# N-H-Bridge.net
KiCad netlist of a schematic drawn in EAGLE
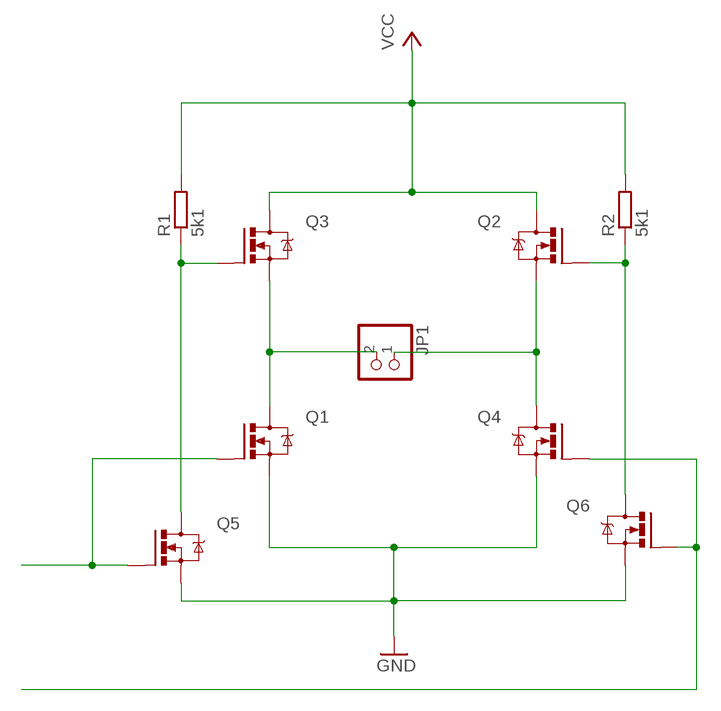
[diagram p0: schematic, sheet 1]

(export (version "E")
  (design (tool "Eeschema 10.0.6"))
  (components
    (comp (ref "JP1")
      (value "PINHD-1X2")
      (footprint "eagle-import:1X02")
      (libsource (lib "eagle-import") (part "PINHD-1X2"))
    )
    (comp (ref "Q1")
      (value "FET-NPF-2X2")
      (footprint "eagle-import:POWERFLAT-2X2")
      (libsource (lib "eagle-import") (part "FET-NPF-2X2"))
    )
    (comp (ref "Q2")
      (value "FET-NPF-2X2")
      (footprint "eagle-import:POWERFLAT-2X2")
      (libsource (lib "eagle-import") (part "FET-NPF-2X2"))
    )
    (comp (ref "Q3")
      (value "FET-NPF-2X2")
      (footprint "eagle-import:POWERFLAT-2X2")
      (libsource (lib "eagle-import") (part "FET-NPF-2X2"))
    )
    (comp (ref "Q4")
      (value "FET-NPF-2X2")
      (footprint "eagle-import:POWERFLAT-2X2")
      (libsource (lib "eagle-import") (part "FET-NPF-2X2"))
    )
    (comp (ref "Q5")
      (value "FET-NPF-2X2")
      (footprint "eagle-import:POWERFLAT-2X2")
      (libsource (lib "eagle-import") (part "FET-NPF-2X2"))
    )
    (comp (ref "Q6")
      (value "FET-NPF-2X2")
      (footprint "eagle-import:POWERFLAT-2X2")
      (libsource (lib "eagle-import") (part "FET-NPF-2X2"))
    )
    (comp (ref "R1")
      (value "5k1")
      (footprint "eagle-import:R0603")
      (libsource (lib "eagle-import") (part "R_0603"))
    )
    (comp (ref "R2")
      (value "5k1")
      (footprint "eagle-import:R0603")
      (libsource (lib "eagle-import") (part "R_0603"))
    )
  )
  (nets
    (net (code "1") (name "GND") (class "Default")
      (node (ref "Q1") (pin "S") (pinfunction "S_S") (pintype "passive"))
      (node (ref "Q1") (pin "S4") (pinfunction "S_S4") (pintype "passive"))
      (node (ref "Q4") (pin "S") (pinfunction "S_S") (pintype "passive"))
      (node (ref "Q4") (pin "S4") (pinfunction "S_S4") (pintype "passive"))
      (node (ref "Q5") (pin "S") (pinfunction "S_S") (pintype "passive"))
      (node (ref "Q5") (pin "S4") (pinfunction "S_S4") (pintype "passive"))
      (node (ref "Q6") (pin "S") (pinfunction "S_S") (pintype "passive"))
      (node (ref "Q6") (pin "S4") (pinfunction "S_S4") (pintype "passive"))
    )
    (net (code "2") (name "Net-(JP1-Pad1)") (class "Default")
      (node (ref "JP1") (pin "1") (pinfunction "1_1") (pintype "passive"))
      (node (ref "Q2") (pin "S") (pinfunction "S_S") (pintype "passive"))
      (node (ref "Q2") (pin "S4") (pinfunction "S_S4") (pintype "passive"))
      (node (ref "Q4") (pin "D") (pinfunction "D_D") (pintype "passive"))
      (node (ref "Q4") (pin "D1") (pinfunction "D_D1") (pintype "passive"))
      (node (ref "Q4") (pin "D2") (pinfunction "D_D2") (pintype "passive"))
      (node (ref "Q4") (pin "D5") (pinfunction "D_D5") (pintype "passive"))
      (node (ref "Q4") (pin "D6") (pinfunction "D_D6") (pintype "passive"))
    )
    (net (code "3") (name "Net-(JP1-Pad2)") (class "Default")
      (node (ref "JP1") (pin "2") (pinfunction "2_2") (pintype "passive"))
      (node (ref "Q1") (pin "D") (pinfunction "D_D") (pintype "passive"))
      (node (ref "Q1") (pin "D1") (pinfunction "D_D1") (pintype "passive"))
      (node (ref "Q1") (pin "D2") (pinfunction "D_D2") (pintype "passive"))
      (node (ref "Q1") (pin "D5") (pinfunction "D_D5") (pintype "passive"))
      (node (ref "Q1") (pin "D6") (pinfunction "D_D6") (pintype "passive"))
      (node (ref "Q3") (pin "S") (pinfunction "S_S") (pintype "passive"))
      (node (ref "Q3") (pin "S4") (pinfunction "S_S4") (pintype "passive"))
    )
    (net (code "4") (name "Net-(Q1-G)") (class "Default")
      (node (ref "Q1") (pin "G3") (pinfunction "G_G3") (pintype "passive"))
      (node (ref "Q5") (pin "G3") (pinfunction "G_G3") (pintype "passive"))
    )
    (net (code "5") (name "Net-(Q2-G)") (class "Default")
      (node (ref "Q2") (pin "G3") (pinfunction "G_G3") (pintype "passive"))
      (node (ref "Q6") (pin "D") (pinfunction "D_D") (pintype "passive"))
      (node (ref "Q6") (pin "D1") (pinfunction "D_D1") (pintype "passive"))
      (node (ref "Q6") (pin "D2") (pinfunction "D_D2") (pintype "passive"))
      (node (ref "Q6") (pin "D5") (pinfunction "D_D5") (pintype "passive"))
      (node (ref "Q6") (pin "D6") (pinfunction "D_D6") (pintype "passive"))
      (node (ref "R2") (pin "1") (pinfunction "1_1") (pintype "passive"))
    )
    (net (code "6") (name "Net-(Q3-G)") (class "Default")
      (node (ref "Q3") (pin "G3") (pinfunction "G_G3") (pintype "passive"))
      (node (ref "Q5") (pin "D") (pinfunction "D_D") (pintype "passive"))
      (node (ref "Q5") (pin "D1") (pinfunction "D_D1") (pintype "passive"))
      (node (ref "Q5") (pin "D2") (pinfunction "D_D2") (pintype "passive"))
      (node (ref "Q5") (pin "D5") (pinfunction "D_D5") (pintype "passive"))
      (node (ref "Q5") (pin "D6") (pinfunction "D_D6") (pintype "passive"))
      (node (ref "R1") (pin "1") (pinfunction "1_1") (pintype "passive"))
    )
    (net (code "7") (name "Net-(Q4-G)") (class "Default")
      (node (ref "Q4") (pin "G3") (pinfunction "G_G3") (pintype "passive"))
      (node (ref "Q6") (pin "G3") (pinfunction "G_G3") (pintype "passive"))
    )
    (net (code "8") (name "VCC") (class "Default")
      (node (ref "Q2") (pin "D") (pinfunction "D_D") (pintype "passive"))
      (node (ref "Q2") (pin "D1") (pinfunction "D_D1") (pintype "passive"))
      (node (ref "Q2") (pin "D2") (pinfunction "D_D2") (pintype "passive"))
      (node (ref "Q2") (pin "D5") (pinfunction "D_D5") (pintype "passive"))
      (node (ref "Q2") (pin "D6") (pinfunction "D_D6") (pintype "passive"))
      (node (ref "Q3") (pin "D") (pinfunction "D_D") (pintype "passive"))
      (node (ref "Q3") (pin "D1") (pinfunction "D_D1") (pintype "passive"))
      (node (ref "Q3") (pin "D2") (pinfunction "D_D2") (pintype "passive"))
      (node (ref "Q3") (pin "D5") (pinfunction "D_D5") (pintype "passive"))
      (node (ref "Q3") (pin "D6") (pinfunction "D_D6") (pintype "passive"))
      (node (ref "R1") (pin "2") (pinfunction "2_2") (pintype "passive"))
      (node (ref "R2") (pin "2") (pinfunction "2_2") (pintype "passive"))
    )
  )
)
